# MCU.net
KiCad netlist of a schematic drawn in Altium Designer
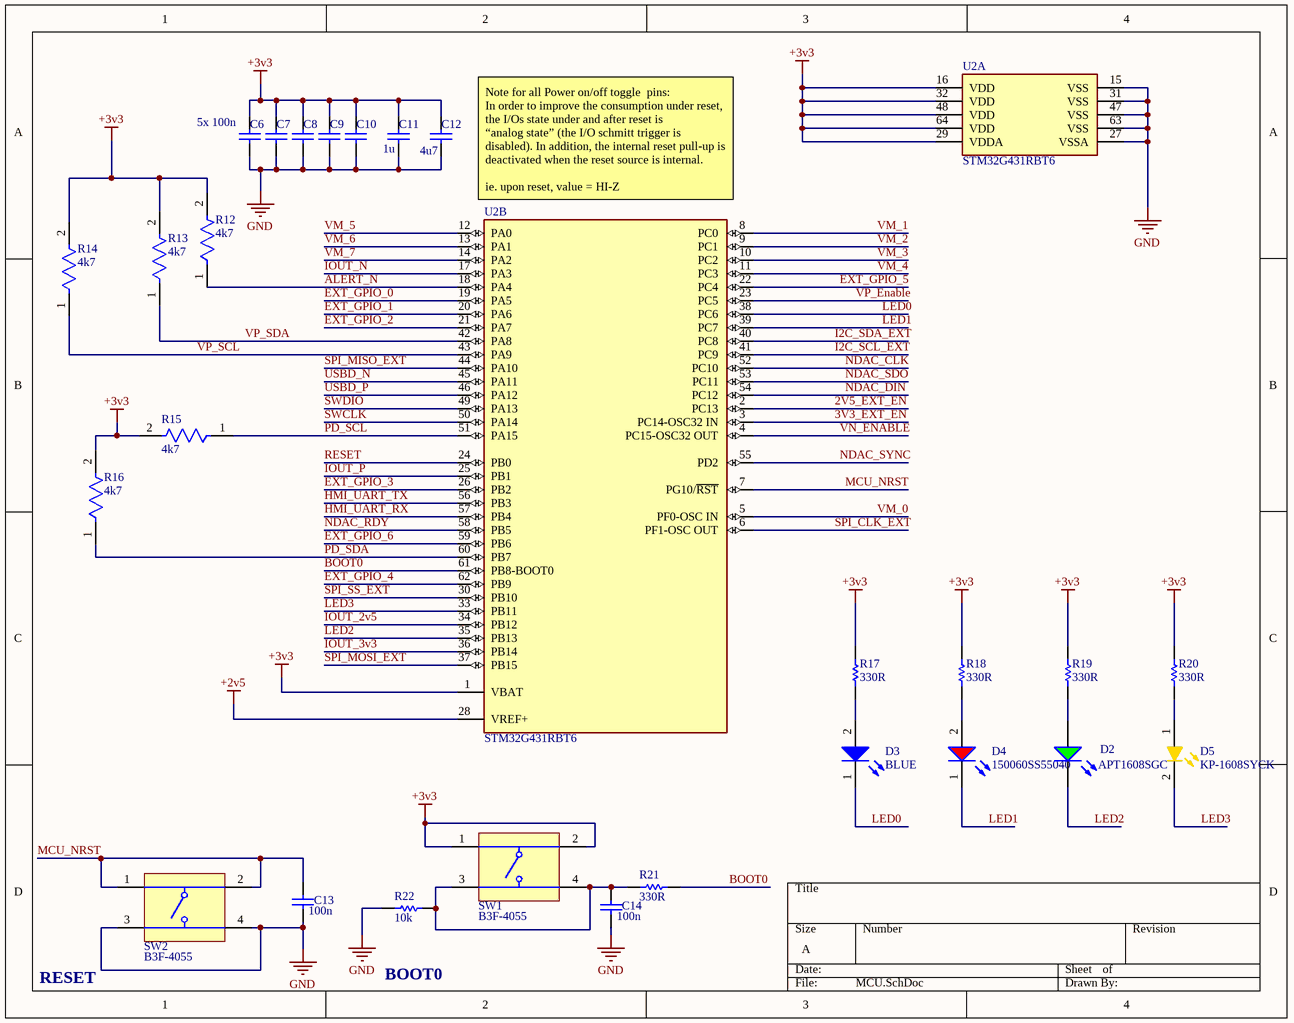
[diagram p0: MCU.SchDoc]

(export (version "E")
  (design (tool "Eeschema 10.0.6"))
  (components
    (comp (ref "C6")
      (value "100n 0805")
      (footprint "CAPC2013X145X50NL20T25")
      (fields (field (name "PART NUMBER") "C0805C106M9RACTU") (field (name "MANUFACTURER") "Kemet"))
      (libsource (lib "Altium Content Vault") (part "CAP"))
    )
    (comp (ref "C7")
      (value "100n 0805")
      (footprint "CAPC2013X145X50NL20T25")
      (fields (field (name "PART NUMBER") "C0805C106M9RACTU") (field (name "MANUFACTURER") "Kemet"))
      (libsource (lib "Altium Content Vault") (part "CAP"))
    )
    (comp (ref "C8")
      (value "100n 0805")
      (footprint "CAPC2013X145X50NL20T25")
      (fields (field (name "PART NUMBER") "C0805C106M9RACTU") (field (name "MANUFACTURER") "Kemet"))
      (libsource (lib "Altium Content Vault") (part "CAP"))
    )
    (comp (ref "C9")
      (value "100n 0805")
      (footprint "CAPC2013X145X50NL20T25")
      (fields (field (name "PART NUMBER") "C0805C106M9RACTU") (field (name "MANUFACTURER") "Kemet"))
      (libsource (lib "Altium Content Vault") (part "CAP"))
    )
    (comp (ref "C10")
      (value "100n 0805")
      (footprint "CAPC2013X145X50NL20T25")
      (fields (field (name "PART NUMBER") "C0805C106M9RACTU") (field (name "MANUFACTURER") "Kemet"))
      (libsource (lib "Altium Content Vault") (part "CAP"))
    )
    (comp (ref "C11")
      (value "1u")
      (footprint "CAPC2013X145X50NL20T25")
      (fields (field (name "PART NUMBER") "C0805C106M9RACTU") (field (name "MANUFACTURER") "Kemet"))
      (libsource (lib "Altium Content Vault") (part "CAP"))
    )
    (comp (ref "C12")
      (value "4u7")
      (footprint "CAPC2013X145X50NL20T25")
      (fields (field (name "PART NUMBER") "C0805C106M9RACTU") (field (name "MANUFACTURER") "Kemet"))
      (libsource (lib "Altium Content Vault") (part "CAP"))
    )
    (comp (ref "C13")
      (value "100n")
      (footprint "CAPC2013X145X50NL20T25")
      (fields (field (name "PART NUMBER") "C0805C106M9RACTU") (field (name "MANUFACTURER") "Kemet"))
      (libsource (lib "Altium Content Vault") (part "CAP"))
    )
    (comp (ref "C14")
      (value "100n")
      (footprint "CAPC2013X145X50NL20T25")
      (fields (field (name "PART NUMBER") "C0805C106M9RACTU") (field (name "MANUFACTURER") "Kemet"))
      (libsource (lib "Altium Content Vault") (part "CAP"))
    )
    (comp (ref "D2")
      (value "APT1608SGC")
      (footprint "KING-APT1608SGC_V")
      (description "Super Bright Green LED, 62.5 mW, 25 mA, -40 to 85 degC, 2-Pin SMD, RoHS, Tape and Reel")
      (fields (field (name "MANUFACTURER") "Kingbright"))
      (libsource (lib "Altium Content Vault") (part "LED-GREEN-AK-2"))
    )
    (comp (ref "D3")
      (value "BLUE")
      (footprint "WL-SMCW_0603_150060xx75000")
      (description "Led, Blue, 470 Nm, 3.2 V, 30 Ma, 145 Mcd Rohs Compliant: Yes")
      (libsource (lib "Altium Content Vault") (part "LED_Blue_2A-1K"))
    )
    (comp (ref "D4")
      (value "150060SS55040")
      (footprint "WL-SMCD_0603")
      (description "150060SS55040 WL-SMCD SMT Mono-color Chip LED Diffused")
      (libsource (lib "Altium Content Vault") (part "LED_Red_2A-1K"))
    )
    (comp (ref "D5")
      (value "KP-1608SYCK")
      (footprint "KING-0603LED_YELLOW_V")
      (description "LED, SMT, 0603(1608), 1.1mm thickness, Yellow")
      (fields (field (name "MANUFACTURER") "Kingbright"))
      (libsource (lib "Altium Content Vault") (part "KING-LED-YELLOW-A1K2-2"))
    )
    (comp (ref "R12")
      (value "4k7")
      (footprint "FP-AC0603-IPC_A")
      (description "RES 4.7KΩ 1.00% 0.1W 0603")
      (fields (field (name "TOLERANCE") "1%"))
      (libsource (lib "Altium Content Vault") (part "1029c3af85768c4190bb7ad29bc67b5"))
    )
    (comp (ref "R13")
      (value "4k7")
      (footprint "FP-AC0603-IPC_A")
      (description "RES 4.7KΩ 1.00% 0.1W 0603")
      (fields (field (name "TOLERANCE") "1%"))
      (libsource (lib "Altium Content Vault") (part "1029c3af85768c4190bb7ad29bc67b5"))
    )
    (comp (ref "R14")
      (value "4k7")
      (footprint "FP-AC0603-IPC_A")
      (description "RES 4.7KΩ 1.00% 0.1W 0603")
      (fields (field (name "TOLERANCE") "1%"))
      (libsource (lib "Altium Content Vault") (part "1029c3af85768c4190bb7ad29bc67b5"))
    )
    (comp (ref "R15")
      (value "4k7")
      (footprint "FP-AC0603-IPC_A")
      (description "RES 4.7KΩ 1.00% 0.1W 0603")
      (fields (field (name "TOLERANCE") "1%"))
      (libsource (lib "Altium Content Vault") (part "1029c3af85768c4190bb7ad29bc67b5"))
    )
    (comp (ref "R16")
      (value "4k7")
      (footprint "FP-AC0603-IPC_A")
      (description "RES 4.7KΩ 1.00% 0.1W 0603")
      (fields (field (name "TOLERANCE") "1%"))
      (libsource (lib "Altium Content Vault") (part "1029c3af85768c4190bb7ad29bc67b5"))
    )
    (comp (ref "R17")
      (value "330R")
      (footprint "RESC1608X55X25NL10T15")
      (description "Chip Resistor, 330 Ohm, +/- 1%, 0.1 W, -55 to 155 degC, 0603 (1608 Metric), RoHS, Tape and Reel")
      (fields (field (name "TOLERANCE") "10%"))
      (libsource (lib "Altium Content Vault") (part "RES-2"))
    )
    (comp (ref "R18")
      (value "330R")
      (footprint "RESC1608X55X25NL10T15")
      (description "Chip Resistor, 330 Ohm, +/- 1%, 0.1 W, -55 to 155 degC, 0603 (1608 Metric), RoHS, Tape and Reel")
      (fields (field (name "TOLERANCE") "10%"))
      (libsource (lib "Altium Content Vault") (part "RES-2"))
    )
    (comp (ref "R19")
      (value "330R")
      (footprint "RESC1608X55X25NL10T15")
      (description "Chip Resistor, 330 Ohm, +/- 1%, 0.1 W, -55 to 155 degC, 0603 (1608 Metric), RoHS, Tape and Reel")
      (fields (field (name "TOLERANCE") "10%"))
      (libsource (lib "Altium Content Vault") (part "RES-2"))
    )
    (comp (ref "R20")
      (value "330R")
      (footprint "RESC1608X55X25NL10T15")
      (description "Chip Resistor, 330 Ohm, +/- 1%, 0.1 W, -55 to 155 degC, 0603 (1608 Metric), RoHS, Tape and Reel")
      (fields (field (name "TOLERANCE") "10%"))
      (libsource (lib "Altium Content Vault") (part "RES-2"))
    )
    (comp (ref "R21")
      (value "330R")
      (footprint "RESC1608X55X30NL15T15")
      (fields (field (name "PART NUMBER") "ERJ-3EKF1502V") (field (name "MANUFACTURER") "Panasonic"))
      (libsource (lib "Altium Content Vault") (part "RES"))
    )
    (comp (ref "R22")
      (value "10k")
      (footprint "RESC1608X55X30NL15T15")
      (fields (field (name "PART NUMBER") "ERJ-3EKF1502V") (field (name "MANUFACTURER") "Panasonic"))
      (libsource (lib "Altium Content Vault") (part "RES"))
    )
    (comp (ref "SW1")
      (value "B3F-4055")
      (footprint "OMRON-B3F-4055_V")
      (description "Tactile Switch, 1 to 50 mA, 100 mOhm Max, 5 to 24 VDC, -25 to 70 degC, 4-Pin THD, RoHS, Bulk")
      (fields (field (name "MANUFACTURER") "OmronElectronics"))
      (libsource (lib "Altium Content Vault") (part "SW-SPST-4_A"))
    )
    (comp (ref "SW2")
      (value "B3F-4055")
      (footprint "OMRON-B3F-4055_V")
      (description "Tactile Switch, 1 to 50 mA, 100 mOhm Max, 5 to 24 VDC, -25 to 70 degC, 4-Pin THD, RoHS, Bulk")
      (fields (field (name "MANUFACTURER") "OmronElectronics"))
      (libsource (lib "Altium Content Vault") (part "SW-SPST-4_A"))
    )
    (comp (ref "U2")
      (value "STM32G431RBT6")
      (footprint "FP-LQFP64-5W-MFG")
      (description "IC MCU 32BIT 128KB FLASH 64LQFP")
      (libsource (lib "Altium Content Vault") (part "d6c5d394e20af6b50f80b096c052b1c"))
    )
  )
  (nets
    (net (code "1") (name "+2v5") (class "Default")
      (node (ref "U2") (pin "28") (pinfunction "VREF+_28") (pintype "power_in"))
    )
    (net (code "2") (name "+3v3") (class "Default")
      (node (ref "C10") (pin "2") (pinfunction "2_2") (pintype "passive"))
      (node (ref "C11") (pin "2") (pinfunction "2_2") (pintype "passive"))
      (node (ref "C12") (pin "2") (pinfunction "2_2") (pintype "passive"))
      (node (ref "C6") (pin "2") (pinfunction "2_2") (pintype "passive"))
      (node (ref "C7") (pin "2") (pinfunction "2_2") (pintype "passive"))
      (node (ref "C8") (pin "2") (pinfunction "2_2") (pintype "passive"))
      (node (ref "C9") (pin "2") (pinfunction "2_2") (pintype "passive"))
      (node (ref "R12") (pin "2") (pinfunction "2_2") (pintype "passive"))
      (node (ref "R13") (pin "2") (pinfunction "2_2") (pintype "passive"))
      (node (ref "R14") (pin "2") (pinfunction "2_2") (pintype "passive"))
      (node (ref "R15") (pin "2") (pinfunction "2_2") (pintype "passive"))
      (node (ref "R16") (pin "2") (pinfunction "2_2") (pintype "passive"))
      (node (ref "R17") (pin "2") (pinfunction "2_2") (pintype "passive"))
      (node (ref "R18") (pin "2") (pinfunction "2_2") (pintype "passive"))
      (node (ref "R19") (pin "2") (pinfunction "2_2") (pintype "passive"))
      (node (ref "R20") (pin "2") (pinfunction "2_2") (pintype "passive"))
      (node (ref "SW1") (pin "1") (pinfunction "1_1") (pintype "passive"))
      (node (ref "SW1") (pin "2") (pinfunction "2_2") (pintype "passive"))
      (node (ref "U2") (pin "1") (pinfunction "VBAT_1") (pintype "power_in"))
      (node (ref "U2") (pin "16") (pinfunction "VDD_16") (pintype "power_in"))
      (node (ref "U2") (pin "29") (pinfunction "VDDA_29") (pintype "power_in"))
      (node (ref "U2") (pin "32") (pinfunction "VDD_32") (pintype "power_in"))
      (node (ref "U2") (pin "48") (pinfunction "VDD_48") (pintype "power_in"))
      (node (ref "U2") (pin "64") (pinfunction "VDD_64") (pintype "power_in"))
    )
    (net (code "3") (name "/2V5_EXT_EN") (class "Default")
      (node (ref "U2") (pin "2") (pinfunction "PC13_2") (pintype "bidirectional"))
    )
    (net (code "4") (name "/3V3_EXT_EN") (class "Default")
      (node (ref "U2") (pin "3") (pinfunction "PC14-OSC32_IN_3") (pintype "bidirectional"))
    )
    (net (code "5") (name "/ALERT_N") (class "Default")
      (node (ref "R12") (pin "1") (pinfunction "1_1") (pintype "passive"))
      (node (ref "U2") (pin "18") (pinfunction "PA4_18") (pintype "bidirectional"))
    )
    (net (code "6") (name "/BOOT0") (class "Default")
      (node (ref "R21") (pin "2") (pinfunction "2_2") (pintype "passive"))
      (node (ref "U2") (pin "61") (pinfunction "PB8-BOOT0_61") (pintype "bidirectional"))
    )
    (net (code "7") (name "/EXT_GPIO_0") (class "Default")
      (node (ref "U2") (pin "19") (pinfunction "PA5_19") (pintype "bidirectional"))
    )
    (net (code "8") (name "/EXT_GPIO_1") (class "Default")
      (node (ref "U2") (pin "20") (pinfunction "PA6_20") (pintype "bidirectional"))
    )
    (net (code "9") (name "/EXT_GPIO_2") (class "Default")
      (node (ref "U2") (pin "21") (pinfunction "PA7_21") (pintype "bidirectional"))
    )
    (net (code "10") (name "/EXT_GPIO_3") (class "Default")
      (node (ref "U2") (pin "26") (pinfunction "PB2_26") (pintype "bidirectional"))
    )
    (net (code "11") (name "/EXT_GPIO_4") (class "Default")
      (node (ref "U2") (pin "62") (pinfunction "PB9_62") (pintype "bidirectional"))
    )
    (net (code "12") (name "/EXT_GPIO_5") (class "Default")
      (node (ref "U2") (pin "22") (pinfunction "PC4_22") (pintype "bidirectional"))
    )
    (net (code "13") (name "/EXT_GPIO_6") (class "Default")
      (node (ref "U2") (pin "59") (pinfunction "PB6_59") (pintype "bidirectional"))
    )
    (net (code "14") (name "/HMI_UART_RX") (class "Default")
      (node (ref "U2") (pin "57") (pinfunction "PB4_57") (pintype "bidirectional"))
    )
    (net (code "15") (name "/HMI_UART_TX") (class "Default")
      (node (ref "U2") (pin "56") (pinfunction "PB3_56") (pintype "bidirectional"))
    )
    (net (code "16") (name "/I2C_SCL_EXT") (class "Default")
      (node (ref "U2") (pin "41") (pinfunction "PC9_41") (pintype "bidirectional"))
    )
    (net (code "17") (name "/I2C_SDA_EXT") (class "Default")
      (node (ref "U2") (pin "40") (pinfunction "PC8_40") (pintype "bidirectional"))
    )
    (net (code "18") (name "/IOUT_2v5") (class "Default")
      (node (ref "U2") (pin "34") (pinfunction "PB12_34") (pintype "bidirectional"))
    )
    (net (code "19") (name "/IOUT_3v3") (class "Default")
      (node (ref "U2") (pin "36") (pinfunction "PB14_36") (pintype "bidirectional"))
    )
    (net (code "20") (name "/IOUT_N") (class "Default")
      (node (ref "U2") (pin "17") (pinfunction "PA3_17") (pintype "bidirectional"))
    )
    (net (code "21") (name "/IOUT_P") (class "Default")
      (node (ref "U2") (pin "25") (pinfunction "PB1_25") (pintype "bidirectional"))
    )
    (net (code "22") (name "/LED0") (class "Default")
      (node (ref "D3") (pin "1") (pinfunction "K_1") (pintype "passive"))
      (node (ref "U2") (pin "38") (pinfunction "PC6_38") (pintype "bidirectional"))
    )
    (net (code "23") (name "/LED1") (class "Default")
      (node (ref "D4") (pin "1") (pinfunction "K_1") (pintype "passive"))
      (node (ref "U2") (pin "39") (pinfunction "PC7_39") (pintype "bidirectional"))
    )
    (net (code "24") (name "/LED2") (class "Default")
      (node (ref "D2") (pin "2") (pinfunction "K_2") (pintype "passive"))
      (node (ref "U2") (pin "35") (pinfunction "PB13_35") (pintype "bidirectional"))
    )
    (net (code "25") (name "/LED3") (class "Default")
      (node (ref "D5") (pin "2") (pinfunction "K_2") (pintype "passive"))
      (node (ref "U2") (pin "33") (pinfunction "PB11_33") (pintype "bidirectional"))
    )
    (net (code "26") (name "/MCU_NRST") (class "Default")
      (node (ref "C13") (pin "2") (pinfunction "2_2") (pintype "passive"))
      (node (ref "SW2") (pin "1") (pinfunction "1_1") (pintype "passive"))
      (node (ref "SW2") (pin "2") (pinfunction "2_2") (pintype "passive"))
      (node (ref "U2") (pin "7") (pinfunction "PG10/~{RST}_7") (pintype "bidirectional"))
    )
    (net (code "27") (name "/NDAC_CLK") (class "Default")
      (node (ref "U2") (pin "52") (pinfunction "PC10_52") (pintype "bidirectional"))
    )
    (net (code "28") (name "/NDAC_DIN") (class "Default")
      (node (ref "U2") (pin "54") (pinfunction "PC12_54") (pintype "bidirectional"))
    )
    (net (code "29") (name "/NDAC_RDY") (class "Default")
      (node (ref "U2") (pin "58") (pinfunction "PB5_58") (pintype "bidirectional"))
    )
    (net (code "30") (name "/NDAC_SDO") (class "Default")
      (node (ref "U2") (pin "53") (pinfunction "PC11_53") (pintype "bidirectional"))
    )
    (net (code "31") (name "/NDAC_SYNC") (class "Default")
      (node (ref "U2") (pin "55") (pinfunction "PD2_55") (pintype "bidirectional"))
    )
    (net (code "32") (name "/PD_SCL") (class "Default")
      (node (ref "R15") (pin "1") (pinfunction "1_1") (pintype "passive"))
      (node (ref "U2") (pin "51") (pinfunction "PA15_51") (pintype "bidirectional"))
    )
    (net (code "33") (name "/PD_SDA") (class "Default")
      (node (ref "R16") (pin "1") (pinfunction "1_1") (pintype "passive"))
      (node (ref "U2") (pin "60") (pinfunction "PB7_60") (pintype "bidirectional"))
    )
    (net (code "34") (name "/RESET") (class "Default")
      (node (ref "U2") (pin "24") (pinfunction "PB0_24") (pintype "bidirectional"))
    )
    (net (code "35") (name "/SPI_CLK_EXT") (class "Default")
      (node (ref "U2") (pin "6") (pinfunction "PF1-OSC_OUT_6") (pintype "bidirectional"))
    )
    (net (code "36") (name "/SPI_MISO_EXT") (class "Default")
      (node (ref "U2") (pin "44") (pinfunction "PA10_44") (pintype "bidirectional"))
    )
    (net (code "37") (name "/SPI_MOSI_EXT") (class "Default")
      (node (ref "U2") (pin "37") (pinfunction "PB15_37") (pintype "bidirectional"))
    )
    (net (code "38") (name "/SPI_SS_EXT") (class "Default")
      (node (ref "U2") (pin "30") (pinfunction "PB10_30") (pintype "bidirectional"))
    )
    (net (code "39") (name "/SWCLK") (class "Default")
      (node (ref "U2") (pin "50") (pinfunction "PA14_50") (pintype "bidirectional"))
    )
    (net (code "40") (name "/SWDIO") (class "Default")
      (node (ref "U2") (pin "49") (pinfunction "PA13_49") (pintype "bidirectional"))
    )
    (net (code "41") (name "/USBD_N") (class "Default")
      (node (ref "U2") (pin "45") (pinfunction "PA11_45") (pintype "bidirectional"))
    )
    (net (code "42") (name "/USBD_P") (class "Default")
      (node (ref "U2") (pin "46") (pinfunction "PA12_46") (pintype "bidirectional"))
    )
    (net (code "43") (name "/VM_0") (class "Default")
      (node (ref "U2") (pin "5") (pinfunction "PF0-OSC_IN_5") (pintype "bidirectional"))
    )
    (net (code "44") (name "/VM_1") (class "Default")
      (node (ref "U2") (pin "8") (pinfunction "PC0_8") (pintype "bidirectional"))
    )
    (net (code "45") (name "/VM_2") (class "Default")
      (node (ref "U2") (pin "9") (pinfunction "PC1_9") (pintype "bidirectional"))
    )
    (net (code "46") (name "/VM_3") (class "Default")
      (node (ref "U2") (pin "10") (pinfunction "PC2_10") (pintype "bidirectional"))
    )
    (net (code "47") (name "/VM_4") (class "Default")
      (node (ref "U2") (pin "11") (pinfunction "PC3_11") (pintype "bidirectional"))
    )
    (net (code "48") (name "/VM_5") (class "Default")
      (node (ref "U2") (pin "12") (pinfunction "PA0_12") (pintype "bidirectional"))
    )
    (net (code "49") (name "/VM_6") (class "Default")
      (node (ref "U2") (pin "13") (pinfunction "PA1_13") (pintype "bidirectional"))
    )
    (net (code "50") (name "/VM_7") (class "Default")
      (node (ref "U2") (pin "14") (pinfunction "PA2_14") (pintype "bidirectional"))
    )
    (net (code "51") (name "/VN_ENABLE") (class "Default")
      (node (ref "U2") (pin "4") (pinfunction "PC15-OSC32_OUT_4") (pintype "bidirectional"))
    )
    (net (code "52") (name "/VP_Enable") (class "Default")
      (node (ref "U2") (pin "23") (pinfunction "PC5_23") (pintype "bidirectional"))
    )
    (net (code "53") (name "/VP_SCL") (class "Default")
      (node (ref "R14") (pin "1") (pinfunction "1_1") (pintype "passive"))
      (node (ref "U2") (pin "43") (pinfunction "PA9_43") (pintype "bidirectional"))
    )
    (net (code "54") (name "/VP_SDA") (class "Default")
      (node (ref "R13") (pin "1") (pinfunction "1_1") (pintype "passive"))
      (node (ref "U2") (pin "42") (pinfunction "PA8_42") (pintype "bidirectional"))
    )
    (net (code "55") (name "GND") (class "Default")
      (node (ref "C10") (pin "1") (pinfunction "1_1") (pintype "passive"))
      (node (ref "C11") (pin "1") (pinfunction "1_1") (pintype "passive"))
      (node (ref "C12") (pin "1") (pinfunction "1_1") (pintype "passive"))
      (node (ref "C13") (pin "1") (pinfunction "1_1") (pintype "passive"))
      (node (ref "C14") (pin "1") (pinfunction "1_1") (pintype "passive"))
      (node (ref "C6") (pin "1") (pinfunction "1_1") (pintype "passive"))
      (node (ref "C7") (pin "1") (pinfunction "1_1") (pintype "passive"))
      (node (ref "C8") (pin "1") (pinfunction "1_1") (pintype "passive"))
      (node (ref "C9") (pin "1") (pinfunction "1_1") (pintype "passive"))
      (node (ref "R22") (pin "1") (pinfunction "1_1") (pintype "passive"))
      (node (ref "SW2") (pin "3") (pinfunction "3_3") (pintype "passive"))
      (node (ref "SW2") (pin "4") (pinfunction "4_4") (pintype "passive"))
      (node (ref "U2") (pin "15") (pinfunction "VSS_15") (pintype "power_in"))
      (node (ref "U2") (pin "27") (pinfunction "VSSA_27") (pintype "power_in"))
      (node (ref "U2") (pin "31") (pinfunction "VSS_31") (pintype "power_in"))
      (node (ref "U2") (pin "47") (pinfunction "VSS_47") (pintype "power_in"))
      (node (ref "U2") (pin "63") (pinfunction "VSS_63") (pintype "power_in"))
    )
    (net (code "56") (name "Net-(C14-Pad2)") (class "Default")
      (node (ref "C14") (pin "2") (pinfunction "2_2") (pintype "passive"))
      (node (ref "R21") (pin "1") (pinfunction "1_1") (pintype "passive"))
      (node (ref "R22") (pin "2") (pinfunction "2_2") (pintype "passive"))
      (node (ref "SW1") (pin "3") (pinfunction "3_3") (pintype "passive"))
      (node (ref "SW1") (pin "4") (pinfunction "4_4") (pintype "passive"))
    )
    (net (code "57") (name "Net-(D2-A)") (class "Default")
      (node (ref "D2") (pin "1") (pinfunction "A_1") (pintype "passive"))
      (node (ref "R19") (pin "1") (pinfunction "1_1") (pintype "passive"))
    )
    (net (code "58") (name "Net-(D3-A)") (class "Default")
      (node (ref "D3") (pin "2") (pinfunction "A_2") (pintype "passive"))
      (node (ref "R17") (pin "1") (pinfunction "1_1") (pintype "passive"))
    )
    (net (code "59") (name "Net-(D4-A)") (class "Default")
      (node (ref "D4") (pin "2") (pinfunction "A_2") (pintype "passive"))
      (node (ref "R18") (pin "1") (pinfunction "1_1") (pintype "passive"))
    )
    (net (code "60") (name "Net-(D5-A)") (class "Default")
      (node (ref "D5") (pin "1") (pinfunction "A_1") (pintype "passive"))
      (node (ref "R20") (pin "1") (pinfunction "1_1") (pintype "passive"))
    )
  )
)
